# wifibasestation.net
KiCad netlist of a schematic drawn in EAGLE
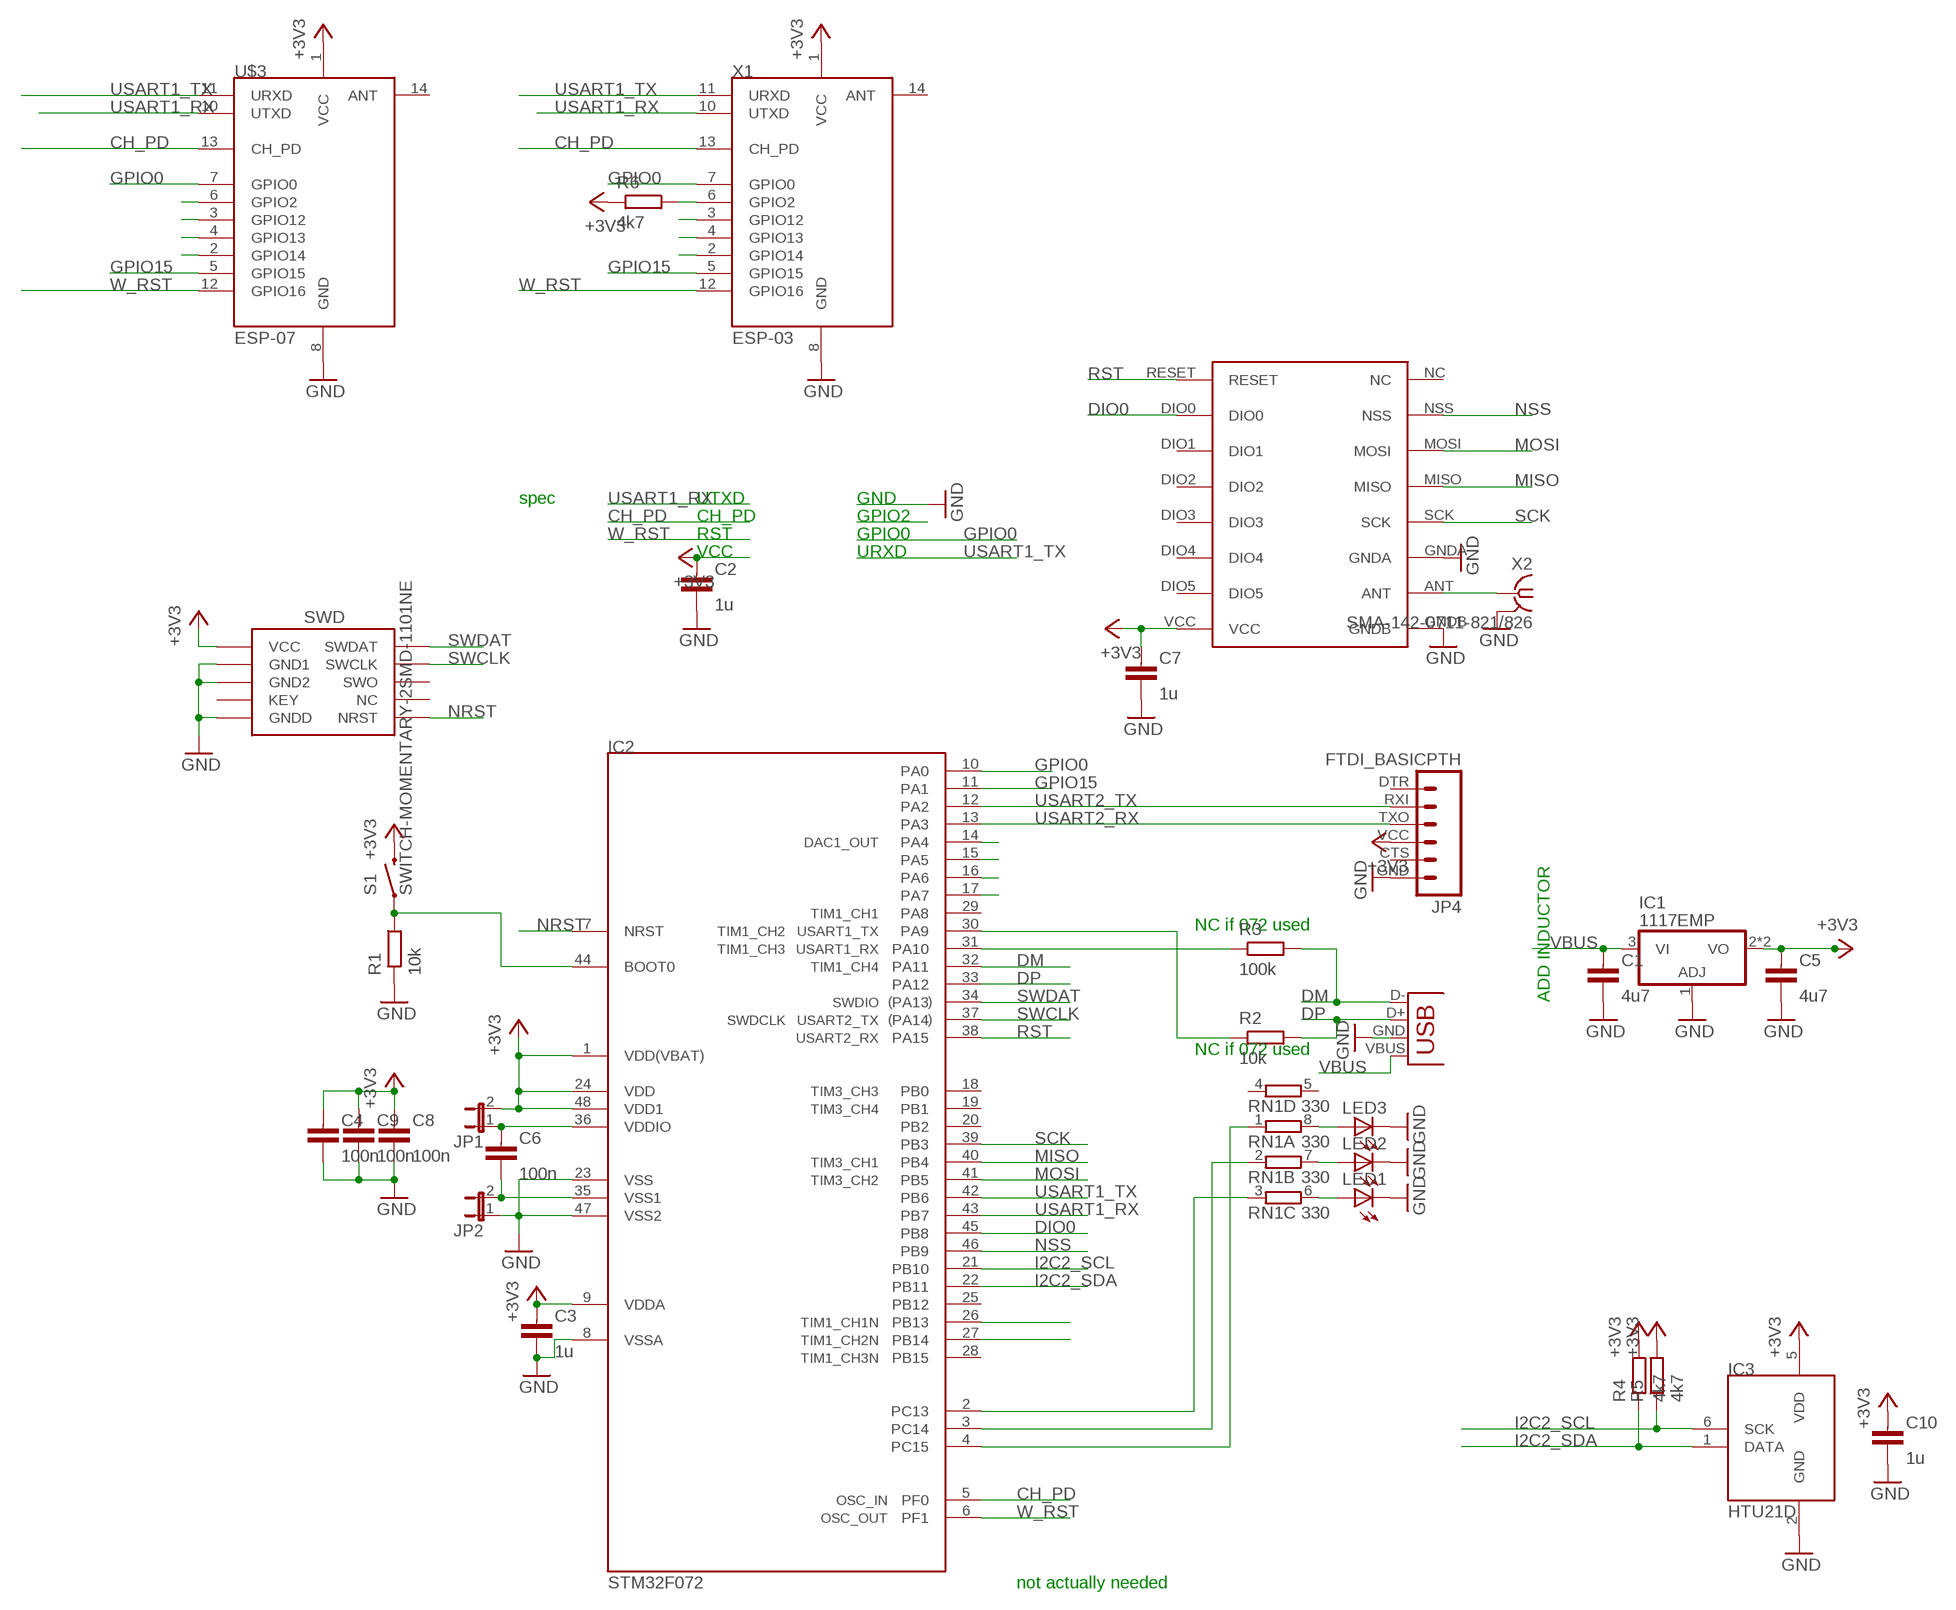
[diagram p0: schematic, sheet 1]

(export (version "E")
  (design (tool "Eeschema 10.0.6"))
  (components
    (comp (ref "C1")
      (value "4u7")
      (footprint "eagle-import:C0603-N")
      (libsource (lib "eagle-import") (part "CAPACITOR0603-N"))
    )
    (comp (ref "C2")
      (value "1u")
      (footprint "eagle-import:C0603-N")
      (libsource (lib "eagle-import") (part "CAPACITOR0603-N"))
    )
    (comp (ref "C3")
      (value "1u")
      (footprint "eagle-import:C0603-N")
      (libsource (lib "eagle-import") (part "CAPACITOR0603-N"))
    )
    (comp (ref "C4")
      (value "100n")
      (footprint "eagle-import:C0603-N")
      (libsource (lib "eagle-import") (part "CAPACITOR0603-N"))
    )
    (comp (ref "C5")
      (value "4u7")
      (footprint "eagle-import:C0805-N")
      (libsource (lib "eagle-import") (part "CAPACITOR0805-N"))
    )
    (comp (ref "C6")
      (value "100n")
      (footprint "eagle-import:C0603-N")
      (libsource (lib "eagle-import") (part "CAPACITOR0603-N"))
    )
    (comp (ref "C7")
      (value "1u")
      (footprint "eagle-import:C0603-N")
      (libsource (lib "eagle-import") (part "CAPACITOR0603-N"))
    )
    (comp (ref "C8")
      (value "100n")
      (footprint "eagle-import:C0603-N")
      (libsource (lib "eagle-import") (part "CAPACITOR0603-N"))
    )
    (comp (ref "C9")
      (value "100n")
      (footprint "eagle-import:C0603-N")
      (libsource (lib "eagle-import") (part "CAPACITOR0603-N"))
    )
    (comp (ref "C10")
      (value "1u")
      (footprint "eagle-import:C0603-N")
      (libsource (lib "eagle-import") (part "CAPACITOR0603-N"))
    )
    (comp (ref "IC1")
      (value "1117EMP")
      (footprint "eagle-import:SOT223")
      (libsource (lib "eagle-import") (part "1117EMP"))
    )
    (comp (ref "IC2")
      (value "STM32F072")
      (footprint "eagle-import:TQFP48")
      (libsource (lib "eagle-import") (part "STM32F072"))
    )
    (comp (ref "IC3")
      (value "HTU21D")
      (footprint "eagle-import:DFN6-L")
      (libsource (lib "eagle-import") (part "HTU21D"))
    )
    (comp (ref "J1")
      (value "SWD_SHROUD_SMD")
      (footprint "eagle-import:SWD_SMD_SHROUD")
      (libsource (lib "eagle-import") (part "SWD_SHROUD_SMD"))
    )
    (comp (ref "JP1")
      (value "JUMPER-2SMD-NC")
      (footprint "eagle-import:SJ_2S")
      (libsource (lib "eagle-import") (part "JUMPER-2SMD-NC"))
    )
    (comp (ref "JP2")
      (value "JUMPER-2SMD-NC")
      (footprint "eagle-import:SJ_2S")
      (libsource (lib "eagle-import") (part "JUMPER-2SMD-NC"))
    )
    (comp (ref "JP3")
      (value "USB-A-H")
      (footprint "eagle-import:USB-A-H")
      (libsource (lib "eagle-import") (part "USB-A-H"))
    )
    (comp (ref "JP4")
      (value "FTDI_BASICPTH")
      (footprint "eagle-import:FTDI_BASIC")
      (libsource (lib "eagle-import") (part "FTDI_BASICPTH"))
    )
    (comp (ref "LED1")
      (value "LEDCHIP-LED0805")
      (footprint "eagle-import:CHIP-LED0805")
      (libsource (lib "eagle-import") (part "LEDCHIP-LED0805"))
    )
    (comp (ref "LED2")
      (value "LEDCHIP-LED0805")
      (footprint "eagle-import:CHIP-LED0805")
      (libsource (lib "eagle-import") (part "LEDCHIP-LED0805"))
    )
    (comp (ref "LED3")
      (value "LEDCHIP-LED0805")
      (footprint "eagle-import:CHIP-LED0805")
      (libsource (lib "eagle-import") (part "LEDCHIP-LED0805"))
    )
    (comp (ref "R1")
      (value "10k")
      (footprint "eagle-import:R0603-N")
      (libsource (lib "eagle-import") (part "RESISTOR0603-N"))
    )
    (comp (ref "R2")
      (value "10k")
      (footprint "eagle-import:R0603-N")
      (libsource (lib "eagle-import") (part "RESISTOR0603-N"))
    )
    (comp (ref "R3")
      (value "100k")
      (footprint "eagle-import:R0603-N")
      (libsource (lib "eagle-import") (part "RESISTOR0603-N"))
    )
    (comp (ref "R4")
      (value "4k7")
      (footprint "eagle-import:R0603-N")
      (libsource (lib "eagle-import") (part "RESISTOR0603-N"))
    )
    (comp (ref "R5")
      (value "4k7")
      (footprint "eagle-import:R0603-N")
      (libsource (lib "eagle-import") (part "RESISTOR0603-N"))
    )
    (comp (ref "R6")
      (value "4k7")
      (footprint "eagle-import:R0603-N")
      (libsource (lib "eagle-import") (part "RESISTOR0603-N"))
    )
    (comp (ref "RN1")
      (value "330")
      (footprint "eagle-import:EXB38V")
      (libsource (lib "eagle-import") (part "4R-NEXB38V"))
    )
    (comp (ref "S1")
      (value "SWITCH-MOMENTARY-2SMD-1101NE")
      (footprint "eagle-import:TACTILE-SWITCH-1101NE")
      (libsource (lib "eagle-import") (part "SWITCH-MOMENTARY-2SMD-1101NE"))
    )
    (comp (ref "U$2")
      (value "RFM69HW")
      (footprint "eagle-import:RFM")
      (libsource (lib "eagle-import") (part "RFM69HW"))
    )
    (comp (ref "U$3")
      (value "ESP-07")
      (footprint "eagle-import:ESP-07")
      (libsource (lib "eagle-import") (part "ESP-07"))
    )
    (comp (ref "X1")
      (value "ESP-03")
      (footprint "eagle-import:ESP-03")
      (libsource (lib "eagle-import") (part "ESP-03"))
    )
    (comp (ref "X2")
      (value "SMA-142-0711-821/826")
      (footprint "eagle-import:J502-ND-142-0711-821_826")
      (fields (field (name "MF") "JOHNSON COMPONENTS") (field (name "MPN") "142-0711-821"))
      (libsource (lib "eagle-import") (part "SMA-142-0711-821/826"))
    )
  )
  (nets
    (net (code "1") (name "+3V3") (class "Default")
      (node (ref "C10") (pin "1") (pinfunction "1_1") (pintype "passive"))
      (node (ref "C2") (pin "1") (pinfunction "1_1") (pintype "passive"))
      (node (ref "C3") (pin "1") (pinfunction "1_1") (pintype "passive"))
      (node (ref "C4") (pin "1") (pinfunction "1_1") (pintype "passive"))
      (node (ref "C5") (pin "1") (pinfunction "1_1") (pintype "passive"))
      (node (ref "C7") (pin "1") (pinfunction "1_1") (pintype "passive"))
      (node (ref "C8") (pin "1") (pinfunction "1_1") (pintype "passive"))
      (node (ref "C9") (pin "1") (pinfunction "1_1") (pintype "passive"))
      (node (ref "IC1") (pin "2") (pinfunction "VO_2") (pintype "passive"))
      (node (ref "IC1") (pin "4") (pinfunction "VO_4") (pintype "passive"))
      (node (ref "IC2") (pin "1") (pinfunction "VDD(VBAT)_1") (pintype "power_in"))
      (node (ref "IC2") (pin "24") (pinfunction "VDD_24") (pintype "power_in"))
      (node (ref "IC2") (pin "48") (pinfunction "VDD1_48") (pintype "power_in"))
      (node (ref "IC2") (pin "9") (pinfunction "VDDA_9") (pintype "power_in"))
      (node (ref "IC3") (pin "5") (pinfunction "VDD_5") (pintype "power_in"))
      (node (ref "J1") (pin "1") (pinfunction "VCC_1") (pintype "power_in"))
      (node (ref "JP1") (pin "2") (pinfunction "2_2") (pintype "passive"))
      (node (ref "JP4") (pin "VCC") (pinfunction "4_VCC") (pintype "passive"))
      (node (ref "R4") (pin "2") (pinfunction "P$2_2") (pintype "passive"))
      (node (ref "R5") (pin "2") (pinfunction "P$2_2") (pintype "passive"))
      (node (ref "R6") (pin "1") (pinfunction "P$1_1") (pintype "passive"))
      (node (ref "S1") (pin "2") (pinfunction "2_2") (pintype "passive"))
      (node (ref "U$2") (pin "VCC") (pinfunction "VCC_VCC") (pintype "bidirectional"))
      (node (ref "U$3") (pin "1") (pinfunction "VCC_1") (pintype "power_in"))
      (node (ref "X1") (pin "1") (pinfunction "VCC_1") (pintype "power_in"))
    )
    (net (code "2") (name "/CH_PD") (class "Default")
      (node (ref "IC2") (pin "5") (pinfunction "PF0_5") (pintype "bidirectional"))
      (node (ref "U$3") (pin "13") (pinfunction "CH_PD_13") (pintype "input"))
      (node (ref "X1") (pin "13") (pinfunction "CH_PD_13") (pintype "input"))
    )
    (net (code "3") (name "/DIO0") (class "Default")
      (node (ref "IC2") (pin "45") (pinfunction "PB8_45") (pintype "bidirectional"))
      (node (ref "U$2") (pin "DIO0") (pinfunction "DIO0_DIO0") (pintype "bidirectional"))
    )
    (net (code "4") (name "/DM") (class "Default")
      (node (ref "IC2") (pin "32") (pinfunction "PA11_32") (pintype "bidirectional"))
      (node (ref "JP3") (pin "D-") (pinfunction "D+_D-") (pintype "bidirectional"))
      (node (ref "R3") (pin "2") (pinfunction "P$2_2") (pintype "passive"))
    )
    (net (code "5") (name "/DP") (class "Default")
      (node (ref "IC2") (pin "33") (pinfunction "PA12_33") (pintype "bidirectional"))
      (node (ref "JP3") (pin "D+") (pinfunction "D-_D+") (pintype "bidirectional"))
      (node (ref "R2") (pin "2") (pinfunction "P$2_2") (pintype "passive"))
    )
    (net (code "6") (name "/GPIO0") (class "Default")
      (node (ref "IC2") (pin "10") (pinfunction "PA0_10") (pintype "bidirectional"))
      (node (ref "U$3") (pin "7") (pinfunction "GPIO0_7") (pintype "bidirectional"))
      (node (ref "X1") (pin "7") (pinfunction "GPIO0_7") (pintype "bidirectional"))
    )
    (net (code "7") (name "/GPIO15") (class "Default")
      (node (ref "IC2") (pin "11") (pinfunction "PA1_11") (pintype "bidirectional"))
      (node (ref "U$3") (pin "5") (pinfunction "GPIO15_5") (pintype "bidirectional"))
      (node (ref "X1") (pin "5") (pinfunction "GPIO15_5") (pintype "bidirectional"))
    )
    (net (code "8") (name "/I2C2_SCL") (class "Default")
      (node (ref "IC2") (pin "21") (pinfunction "PB10_21") (pintype "bidirectional"))
      (node (ref "IC3") (pin "6") (pinfunction "SCK_6") (pintype "input"))
      (node (ref "R5") (pin "1") (pinfunction "P$1_1") (pintype "passive"))
    )
    (net (code "9") (name "/I2C2_SDA") (class "Default")
      (node (ref "IC2") (pin "22") (pinfunction "PB11_22") (pintype "bidirectional"))
      (node (ref "IC3") (pin "1") (pinfunction "DATA_1") (pintype "bidirectional"))
      (node (ref "R4") (pin "1") (pinfunction "P$1_1") (pintype "passive"))
    )
    (net (code "10") (name "/MISO") (class "Default")
      (node (ref "IC2") (pin "40") (pinfunction "PB4_40") (pintype "bidirectional"))
      (node (ref "U$2") (pin "MISO") (pinfunction "MISO_MISO") (pintype "bidirectional"))
    )
    (net (code "11") (name "/MOSI") (class "Default")
      (node (ref "IC2") (pin "41") (pinfunction "PB5_41") (pintype "bidirectional"))
      (node (ref "U$2") (pin "MOSI") (pinfunction "MOSI_MOSI") (pintype "bidirectional"))
    )
    (net (code "12") (name "/N$1") (class "Default")
      (node (ref "R6") (pin "2") (pinfunction "P$2_2") (pintype "passive"))
      (node (ref "U$3") (pin "6") (pinfunction "GPIO2_6") (pintype "bidirectional"))
      (node (ref "X1") (pin "6") (pinfunction "GPIO2_6") (pintype "bidirectional"))
    )
    (net (code "13") (name "/N$3") (class "Default")
      (node (ref "U$3") (pin "2") (pinfunction "GPIO14_2") (pintype "bidirectional"))
      (node (ref "X1") (pin "2") (pinfunction "GPIO14_2") (pintype "bidirectional"))
    )
    (net (code "14") (name "/N$4") (class "Default")
      (node (ref "U$3") (pin "4") (pinfunction "GPIO13_4") (pintype "bidirectional"))
      (node (ref "X1") (pin "4") (pinfunction "GPIO13_4") (pintype "bidirectional"))
    )
    (net (code "15") (name "/N$7") (class "Default")
      (node (ref "U$3") (pin "3") (pinfunction "GPIO12_3") (pintype "bidirectional"))
      (node (ref "X1") (pin "3") (pinfunction "GPIO12_3") (pintype "bidirectional"))
    )
    (net (code "16") (name "/NRST") (class "Default")
      (node (ref "IC2") (pin "7") (pinfunction "NRST_7") (pintype "input"))
      (node (ref "J1") (pin "10") (pinfunction "NRST_10") (pintype "bidirectional"))
    )
    (net (code "17") (name "/NSS") (class "Default")
      (node (ref "IC2") (pin "46") (pinfunction "PB9_46") (pintype "bidirectional"))
      (node (ref "U$2") (pin "NSS") (pinfunction "NSS_NSS") (pintype "bidirectional"))
    )
    (net (code "18") (name "/RST") (class "Default")
      (node (ref "IC2") (pin "38") (pinfunction "PA15_38") (pintype "bidirectional"))
      (node (ref "U$2") (pin "RESET") (pinfunction "RESET_RESET") (pintype "bidirectional"))
    )
    (net (code "19") (name "/SCK") (class "Default")
      (node (ref "IC2") (pin "39") (pinfunction "PB3_39") (pintype "bidirectional"))
      (node (ref "U$2") (pin "SCK") (pinfunction "SCK_SCK") (pintype "bidirectional"))
    )
    (net (code "20") (name "/SWCLK") (class "Default")
      (node (ref "IC2") (pin "37") (pinfunction "PA14_37") (pintype "bidirectional"))
      (node (ref "J1") (pin "4") (pinfunction "SWCLK_4") (pintype "bidirectional"))
    )
    (net (code "21") (name "/SWDAT") (class "Default")
      (node (ref "IC2") (pin "34") (pinfunction "PA13_34") (pintype "bidirectional"))
      (node (ref "J1") (pin "2") (pinfunction "SWDAT_2") (pintype "bidirectional"))
    )
    (net (code "22") (name "/USART1_RX") (class "Default")
      (node (ref "IC2") (pin "43") (pinfunction "PB7_43") (pintype "bidirectional"))
      (node (ref "U$3") (pin "10") (pinfunction "UTXD_10") (pintype "output"))
      (node (ref "X1") (pin "10") (pinfunction "UTXD_10") (pintype "output"))
    )
    (net (code "23") (name "/USART1_TX") (class "Default")
      (node (ref "IC2") (pin "42") (pinfunction "PB6_42") (pintype "bidirectional"))
      (node (ref "U$3") (pin "11") (pinfunction "URXD_11") (pintype "input"))
      (node (ref "X1") (pin "11") (pinfunction "URXD_11") (pintype "input"))
    )
    (net (code "24") (name "/USART2_RX") (class "Default")
      (node (ref "IC2") (pin "13") (pinfunction "PA3_13") (pintype "bidirectional"))
      (node (ref "JP4") (pin "TXO") (pinfunction "3_TXO") (pintype "passive"))
    )
    (net (code "25") (name "/USART2_TX") (class "Default")
      (node (ref "IC2") (pin "12") (pinfunction "PA2_12") (pintype "bidirectional"))
      (node (ref "JP4") (pin "RXI") (pinfunction "2_RXI") (pintype "passive"))
    )
    (net (code "26") (name "/VBUS") (class "Default")
      (node (ref "C1") (pin "1") (pinfunction "1_1") (pintype "passive"))
      (node (ref "IC1") (pin "3") (pinfunction "VI_3") (pintype "input"))
      (node (ref "JP3") (pin "VBUS") (pinfunction "GND_VBUS") (pintype "bidirectional"))
    )
    (net (code "27") (name "/W_RST") (class "Default")
      (node (ref "IC2") (pin "6") (pinfunction "PF1_6") (pintype "bidirectional"))
      (node (ref "U$3") (pin "12") (pinfunction "GPIO16_12") (pintype "bidirectional"))
      (node (ref "X1") (pin "12") (pinfunction "GPIO16_12") (pintype "bidirectional"))
    )
    (net (code "28") (name "GND") (class "Default")
      (node (ref "C1") (pin "2") (pinfunction "2_2") (pintype "passive"))
      (node (ref "C10") (pin "2") (pinfunction "2_2") (pintype "passive"))
      (node (ref "C2") (pin "2") (pinfunction "2_2") (pintype "passive"))
      (node (ref "C3") (pin "2") (pinfunction "2_2") (pintype "passive"))
      (node (ref "C4") (pin "2") (pinfunction "2_2") (pintype "passive"))
      (node (ref "C5") (pin "2") (pinfunction "2_2") (pintype "passive"))
      (node (ref "C7") (pin "2") (pinfunction "2_2") (pintype "passive"))
      (node (ref "C8") (pin "2") (pinfunction "2_2") (pintype "passive"))
      (node (ref "C9") (pin "2") (pinfunction "2_2") (pintype "passive"))
      (node (ref "IC1") (pin "1") (pinfunction "ADJ_1") (pintype "input"))
      (node (ref "IC2") (pin "23") (pinfunction "VSS_23") (pintype "power_in"))
      (node (ref "IC2") (pin "47") (pinfunction "VSS2_47") (pintype "power_in"))
      (node (ref "IC2") (pin "8") (pinfunction "VSSA_8") (pintype "power_in"))
      (node (ref "IC3") (pin "2") (pinfunction "GND_2") (pintype "power_in"))
      (node (ref "J1") (pin "3") (pinfunction "GND1_3") (pintype "power_in"))
      (node (ref "J1") (pin "5") (pinfunction "GND2_5") (pintype "power_in"))
      (node (ref "J1") (pin "9") (pinfunction "GNDD_9") (pintype "power_in"))
      (node (ref "JP2") (pin "1") (pinfunction "1_1") (pintype "passive"))
      (node (ref "JP3") (pin "GND") (pinfunction "VBUS_GND") (pintype "bidirectional"))
      (node (ref "JP4") (pin "GND") (pinfunction "6_GND") (pintype "passive"))
      (node (ref "LED1") (pin "C") (pinfunction "C_C") (pintype "passive"))
      (node (ref "LED2") (pin "C") (pinfunction "C_C") (pintype "passive"))
      (node (ref "LED3") (pin "C") (pinfunction "C_C") (pintype "passive"))
      (node (ref "R1") (pin "1") (pinfunction "P$1_1") (pintype "passive"))
      (node (ref "U$2") (pin "GNDA") (pinfunction "GNDA_GNDA") (pintype "bidirectional"))
      (node (ref "U$2") (pin "GNDB") (pinfunction "GNDB_GNDB") (pintype "bidirectional"))
      (node (ref "U$3") (pin "8") (pinfunction "GND_8") (pintype "power_in"))
      (node (ref "X1") (pin "8") (pinfunction "GND_8") (pintype "power_in"))
      (node (ref "X2") (pin "G@1") (pinfunction "2_G@1") (pintype "passive"))
      (node (ref "X2") (pin "G@2") (pinfunction "2_G@2") (pintype "passive"))
      (node (ref "X2") (pin "G@3") (pinfunction "2_G@3") (pintype "passive"))
      (node (ref "X2") (pin "G@4") (pinfunction "2_G@4") (pintype "passive"))
    )
    (net (code "29") (name "Net-(IC2-BOOT0)") (class "Default")
      (node (ref "IC2") (pin "44") (pinfunction "BOOT0_44") (pintype "input"))
      (node (ref "R1") (pin "2") (pinfunction "P$2_2") (pintype "passive"))
      (node (ref "S1") (pin "1") (pinfunction "1_1") (pintype "passive"))
    )
    (net (code "30") (name "Net-(IC2-PA9)") (class "Default")
      (node (ref "IC2") (pin "30") (pinfunction "PA9_30") (pintype "bidirectional"))
      (node (ref "R2") (pin "1") (pinfunction "P$1_1") (pintype "passive"))
    )
    (net (code "31") (name "Net-(IC2-PA10)") (class "Default")
      (node (ref "IC2") (pin "31") (pinfunction "PA10_31") (pintype "bidirectional"))
      (node (ref "R3") (pin "1") (pinfunction "P$1_1") (pintype "passive"))
    )
    (net (code "32") (name "Net-(IC2-PC13)") (class "Default")
      (node (ref "IC2") (pin "2") (pinfunction "PC13_2") (pintype "bidirectional"))
      (node (ref "RN1") (pin "3") (pinfunction "1_3") (pintype "passive"))
    )
    (net (code "33") (name "Net-(IC2-PC14)") (class "Default")
      (node (ref "IC2") (pin "3") (pinfunction "PC14_3") (pintype "bidirectional"))
      (node (ref "RN1") (pin "2") (pinfunction "1_2") (pintype "passive"))
    )
    (net (code "34") (name "Net-(IC2-PC15)") (class "Default")
      (node (ref "IC2") (pin "4") (pinfunction "PC15_4") (pintype "bidirectional"))
      (node (ref "RN1") (pin "1") (pinfunction "1_1") (pintype "passive"))
    )
    (net (code "35") (name "Net-(IC2-VDDIO)") (class "Default")
      (node (ref "C6") (pin "1") (pinfunction "1_1") (pintype "passive"))
      (node (ref "IC2") (pin "36") (pinfunction "VDDIO_36") (pintype "power_in"))
      (node (ref "JP1") (pin "1") (pinfunction "1_1") (pintype "passive"))
    )
    (net (code "36") (name "Net-(IC2-VSS1)") (class "Default")
      (node (ref "C6") (pin "2") (pinfunction "2_2") (pintype "passive"))
      (node (ref "IC2") (pin "35") (pinfunction "VSS1_35") (pintype "power_in"))
      (node (ref "JP2") (pin "2") (pinfunction "2_2") (pintype "passive"))
    )
    (net (code "37") (name "Net-(RN1A-2)") (class "Default")
      (node (ref "LED3") (pin "A") (pinfunction "A_A") (pintype "passive"))
      (node (ref "RN1") (pin "8") (pinfunction "2_8") (pintype "passive"))
    )
    (net (code "38") (name "Net-(RN1B-2)") (class "Default")
      (node (ref "LED2") (pin "A") (pinfunction "A_A") (pintype "passive"))
      (node (ref "RN1") (pin "7") (pinfunction "2_7") (pintype "passive"))
    )
    (net (code "39") (name "Net-(RN1C-2)") (class "Default")
      (node (ref "LED1") (pin "A") (pinfunction "A_A") (pintype "passive"))
      (node (ref "RN1") (pin "6") (pinfunction "2_6") (pintype "passive"))
    )
    (net (code "40") (name "Net-(U$2-PadANT)") (class "Default")
      (node (ref "U$2") (pin "ANT") (pinfunction "ANT_ANT") (pintype "bidirectional"))
      (node (ref "X2") (pin "1") (pinfunction "1_1") (pintype "passive"))
    )
    (net (code "41") (name "unconnected-(IC2-PA4-Pad14)") (class "Default")
      (node (ref "IC2") (pin "14") (pinfunction "PA4_14") (pintype "bidirectional"))
    )
    (net (code "42") (name "unconnected-(IC2-PA5-Pad15)") (class "Default")
      (node (ref "IC2") (pin "15") (pinfunction "PA5_15") (pintype "bidirectional"))
    )
    (net (code "43") (name "unconnected-(IC2-PA6-Pad16)") (class "Default")
      (node (ref "IC2") (pin "16") (pinfunction "PA6_16") (pintype "bidirectional"))
    )
    (net (code "44") (name "unconnected-(IC2-PA7-Pad17)") (class "Default")
      (node (ref "IC2") (pin "17") (pinfunction "PA7_17") (pintype "bidirectional"))
    )
    (net (code "45") (name "unconnected-(IC2-PA8-Pad29)") (class "Default")
      (node (ref "IC2") (pin "29") (pinfunction "PA8_29") (pintype "bidirectional"))
    )
    (net (code "46") (name "unconnected-(IC2-PB0-Pad18)") (class "Default")
      (node (ref "IC2") (pin "18") (pinfunction "PB0_18") (pintype "bidirectional"))
    )
    (net (code "47") (name "unconnected-(IC2-PB1-Pad19)") (class "Default")
      (node (ref "IC2") (pin "19") (pinfunction "PB1_19") (pintype "bidirectional"))
    )
    (net (code "48") (name "unconnected-(IC2-PB2-Pad20)") (class "Default")
      (node (ref "IC2") (pin "20") (pinfunction "PB2_20") (pintype "bidirectional"))
    )
    (net (code "49") (name "unconnected-(IC2-PB12-Pad25)") (class "Default")
      (node (ref "IC2") (pin "25") (pinfunction "PB12_25") (pintype "bidirectional"))
    )
    (net (code "50") (name "unconnected-(IC2-PB13-Pad26)") (class "Default")
      (node (ref "IC2") (pin "26") (pinfunction "PB13_26") (pintype "bidirectional"))
    )
    (net (code "51") (name "unconnected-(IC2-PB14-Pad27)") (class "Default")
      (node (ref "IC2") (pin "27") (pinfunction "PB14_27") (pintype "bidirectional"))
    )
    (net (code "52") (name "unconnected-(IC2-PB15-Pad28)") (class "Default")
      (node (ref "IC2") (pin "28") (pinfunction "PB15_28") (pintype "bidirectional"))
    )
    (net (code "53") (name "unconnected-(J1-KEY-Pad7)") (class "Default")
      (node (ref "J1") (pin "7") (pinfunction "KEY_7") (pintype "bidirectional"))
    )
    (net (code "54") (name "unconnected-(J1-NC-Pad8)") (class "Default")
      (node (ref "J1") (pin "8") (pinfunction "NC_8") (pintype "no_connect"))
    )
    (net (code "55") (name "unconnected-(J1-SWO-Pad6)") (class "Default")
      (node (ref "J1") (pin "6") (pinfunction "SWO_6") (pintype "bidirectional"))
    )
    (net (code "56") (name "unconnected-(JP4-1-PadDTR)") (class "Default")
      (node (ref "JP4") (pin "DTR") (pinfunction "1_DTR") (pintype "passive"))
    )
    (net (code "57") (name "unconnected-(JP4-5-PadCTS)") (class "Default")
      (node (ref "JP4") (pin "CTS") (pinfunction "5_CTS") (pintype "passive"))
    )
    (net (code "58") (name "unconnected-(RN1D-1-Pad4)") (class "Default")
      (node (ref "RN1") (pin "4") (pinfunction "1_4") (pintype "passive"))
    )
    (net (code "59") (name "unconnected-(RN1D-2-Pad5)") (class "Default")
      (node (ref "RN1") (pin "5") (pinfunction "2_5") (pintype "passive"))
    )
    (net (code "60") (name "unconnected-(U$2-PadDIO1)") (class "Default")
      (node (ref "U$2") (pin "DIO1") (pinfunction "DIO1_DIO1") (pintype "bidirectional"))
    )
    (net (code "61") (name "unconnected-(U$2-PadDIO2)") (class "Default")
      (node (ref "U$2") (pin "DIO2") (pinfunction "DIO2_DIO2") (pintype "bidirectional"))
    )
    (net (code "62") (name "unconnected-(U$2-PadDIO3)") (class "Default")
      (node (ref "U$2") (pin "DIO3") (pinfunction "DIO3_DIO3") (pintype "bidirectional"))
    )
    (net (code "63") (name "unconnected-(U$2-PadDIO4)") (class "Default")
      (node (ref "U$2") (pin "DIO4") (pinfunction "DIO4_DIO4") (pintype "bidirectional"))
    )
    (net (code "64") (name "unconnected-(U$2-PadDIO5)") (class "Default")
      (node (ref "U$2") (pin "DIO5") (pinfunction "DIO5_DIO5") (pintype "bidirectional"))
    )
    (net (code "65") (name "unconnected-(U$2-PadNC)") (class "Default")
      (node (ref "U$2") (pin "NC") (pinfunction "NC_NC") (pintype "bidirectional"))
    )
    (net (code "66") (name "unconnected-(U$3-ANT-Pad14)") (class "Default")
      (node (ref "U$3") (pin "14") (pinfunction "ANT_14") (pintype "bidirectional"))
    )
    (net (code "67") (name "unconnected-(X1-ANT-Pad14)") (class "Default")
      (node (ref "X1") (pin "14") (pinfunction "ANT_14") (pintype "bidirectional"))
    )
  )
)
